# Sheet1.net
KiCad netlist of a schematic drawn in Altium Designer
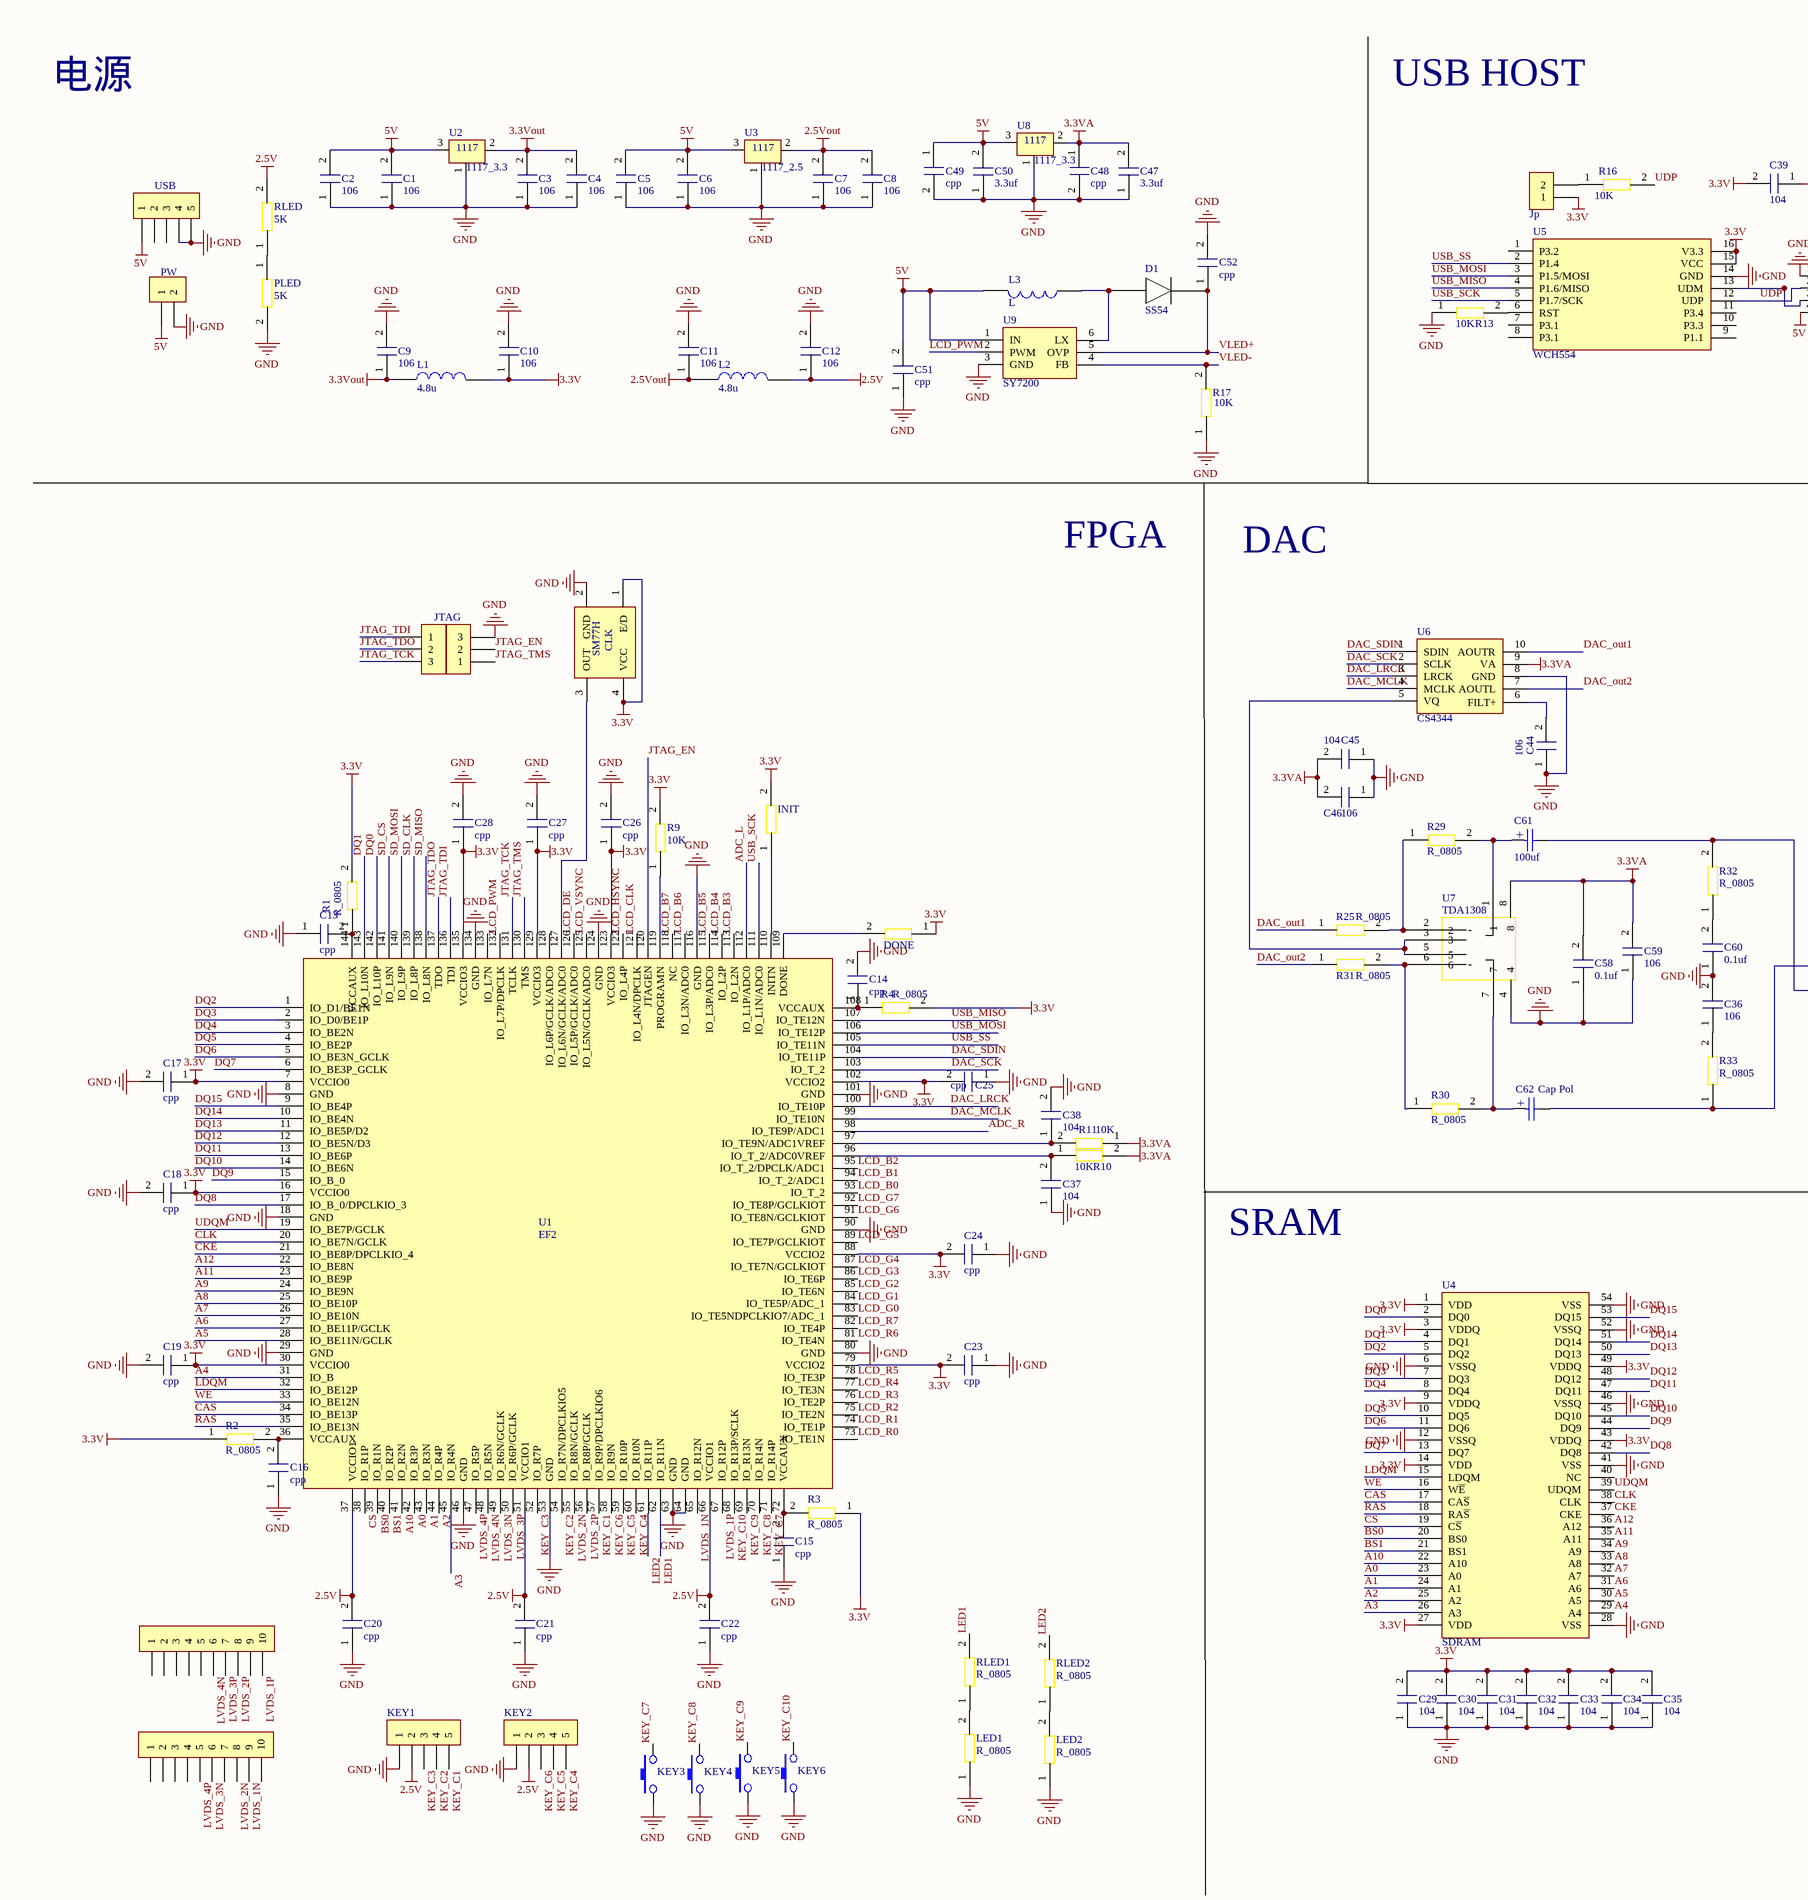
[diagram p0: Sheet1.SchDoc, left]
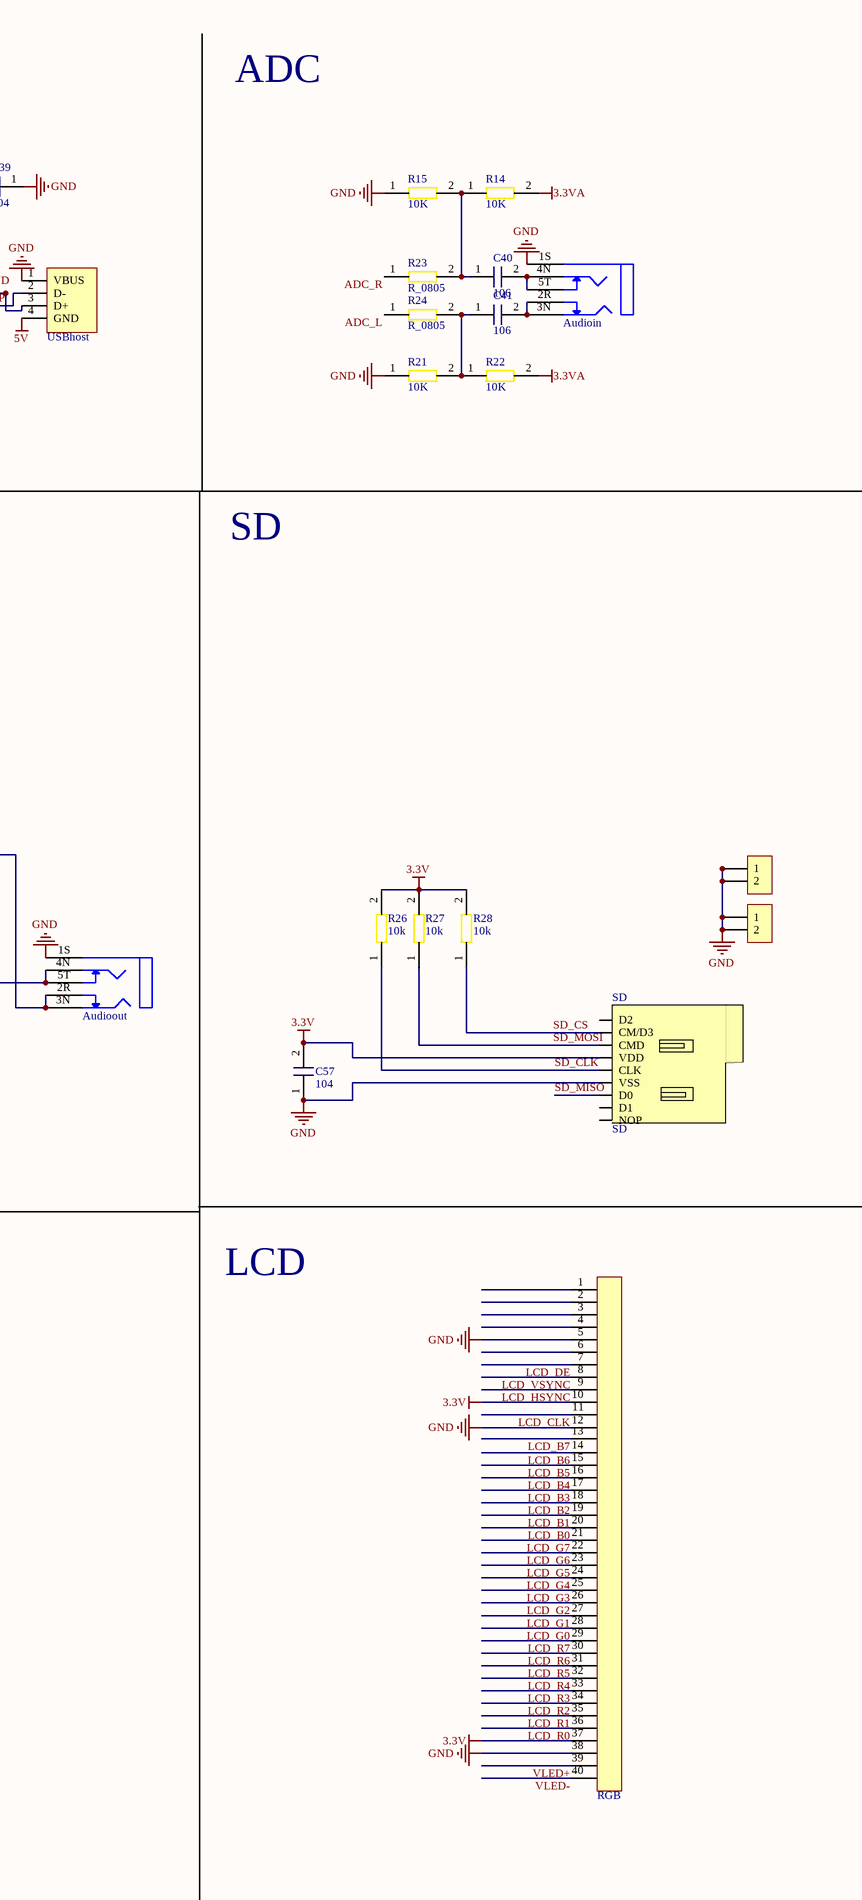
[diagram p1: Sheet1.SchDoc, right]

(export (version "E")
  (design (tool "Eeschema 10.0.6"))
  (components
    (comp (ref "Audioin") (value "Audio") (footprint "AUDIO") (libsource (lib "数字调频收音机") (part "Audio")))
    (comp (ref "Audioout") (value "Audio") (footprint "AUDIO") (libsource (lib "数字调频收音机") (part "Audio")))
    (comp (ref "brg") (value "CON10") (footprint "sip10") (libsource (lib "常用元件库") (part "CON10")))
    (comp (ref "brg1") (value "CON10") (footprint "sip10") (libsource (lib "常用元件库") (part "CON10")))
    (comp (ref "brg2") (value "CON2") (footprint "SIP2") (libsource (lib "常用元件库") (part "CON2")))
    (comp (ref "brg4") (value "CON2") (footprint "SIP2") (libsource (lib "常用元件库") (part "CON2")))
    (comp (ref "C1") (value "106") (footprint "电容器") (libsource (lib "常用") (part "cpp")))
    (comp (ref "C2") (value "106") (footprint "电容器") (libsource (lib "常用") (part "cpp")))
    (comp (ref "C3") (value "106") (footprint "电容器") (libsource (lib "常用") (part "cpp")))
    (comp (ref "C4") (value "106") (footprint "电容器") (libsource (lib "常用") (part "cpp")))
    (comp (ref "C5") (value "106") (footprint "电容器") (libsource (lib "常用") (part "cpp")))
    (comp (ref "C6") (value "106") (footprint "电容器") (libsource (lib "常用") (part "cpp")))
    (comp (ref "C7") (value "106") (footprint "电容器") (libsource (lib "常用") (part "cpp")))
    (comp (ref "C8") (value "106") (footprint "电容器") (libsource (lib "常用") (part "cpp")))
    (comp (ref "C9") (value "106") (footprint "电容器") (libsource (lib "常用") (part "cpp")))
    (comp (ref "C10") (value "106") (footprint "电容器") (libsource (lib "常用") (part "cpp")))
    (comp (ref "C11") (value "106") (footprint "电容器") (libsource (lib "常用") (part "cpp")))
    (comp (ref "C12") (value "106") (footprint "电容器") (libsource (lib "常用") (part "cpp")))
    (comp (ref "C13") (value "cpp") (footprint "电容器") (libsource (lib "常用") (part "cpp")))
    (comp (ref "C14") (value "cpp") (footprint "电容器") (libsource (lib "常用") (part "cpp")))
    (comp (ref "C15") (value "cpp") (footprint "电容器") (libsource (lib "常用") (part "cpp")))
    (comp (ref "C16") (value "cpp") (footprint "电容器") (libsource (lib "常用") (part "cpp")))
    (comp (ref "C17") (value "cpp") (footprint "电容器") (libsource (lib "常用") (part "cpp")))
    (comp (ref "C18") (value "cpp") (footprint "电容器") (libsource (lib "常用") (part "cpp")))
    (comp (ref "C19") (value "cpp") (footprint "电容器") (libsource (lib "常用") (part "cpp")))
    (comp (ref "C20") (value "cpp") (footprint "电容器") (libsource (lib "常用") (part "cpp")))
    (comp (ref "C21") (value "cpp") (footprint "电容器") (libsource (lib "常用") (part "cpp")))
    (comp (ref "C22") (value "cpp") (footprint "电容器") (libsource (lib "常用") (part "cpp")))
    (comp (ref "C23") (value "cpp") (footprint "电容器") (libsource (lib "常用") (part "cpp")))
    (comp (ref "C24") (value "cpp") (footprint "电容器") (libsource (lib "常用") (part "cpp")))
    (comp (ref "C25") (value "cpp") (footprint "电容器") (libsource (lib "常用") (part "cpp")))
    (comp (ref "C26") (value "cpp") (footprint "电容器") (libsource (lib "常用") (part "cpp")))
    (comp (ref "C27") (value "cpp") (footprint "电容器") (libsource (lib "常用") (part "cpp")))
    (comp (ref "C28") (value "cpp") (footprint "电容器") (libsource (lib "常用") (part "cpp")))
    (comp (ref "C29") (value "104") (footprint "电容器") (libsource (lib "常用") (part "cpp")))
    (comp (ref "C30") (value "104") (footprint "电容器") (libsource (lib "常用") (part "cpp")))
    (comp (ref "C31") (value "104") (footprint "电容器") (libsource (lib "常用") (part "cpp")))
    (comp (ref "C32") (value "104") (footprint "电容器") (libsource (lib "常用") (part "cpp")))
    (comp (ref "C33") (value "104") (footprint "电容器") (libsource (lib "常用") (part "cpp")))
    (comp (ref "C34") (value "104") (footprint "电容器") (libsource (lib "常用") (part "cpp")))
    (comp (ref "C35") (value "104") (footprint "电容器") (libsource (lib "常用") (part "cpp")))
    (comp (ref "C36") (value "106") (footprint "电容器") (libsource (lib "常用") (part "cpp")))
    (comp (ref "C37") (value "104") (footprint "电容器") (libsource (lib "常用") (part "cpp")))
    (comp (ref "C38") (value "104") (footprint "电容器") (libsource (lib "常用") (part "cpp")))
    (comp (ref "C39") (value "104") (footprint "电容器") (libsource (lib "常用") (part "cpp")))
    (comp (ref "C40") (value "106") (footprint "电容器") (libsource (lib "常用") (part "cpp")))
    (comp (ref "C41") (value "106") (footprint "电容器") (libsource (lib "常用") (part "cpp")))
    (comp (ref "C44") (value "106") (footprint "电容器") (libsource (lib "常用") (part "cpp")))
    (comp (ref "C45") (value "104") (footprint "电容器") (libsource (lib "常用") (part "cpp")))
    (comp (ref "C46") (value "106") (footprint "电容器") (libsource (lib "常用") (part "cpp")))
    (comp (ref "C47") (value "3.3uf") (footprint "电容器") (libsource (lib "常用") (part "cpp")))
    (comp (ref "C48") (value "cpp") (footprint "电容器") (libsource (lib "常用") (part "cpp")))
    (comp (ref "C49") (value "cpp") (footprint "电容器") (libsource (lib "常用") (part "cpp")))
    (comp (ref "C50") (value "3.3uf") (footprint "电容器") (libsource (lib "常用") (part "cpp")))
    (comp (ref "C51") (value "cpp") (footprint "电容器") (libsource (lib "常用") (part "cpp")))
    (comp (ref "C52") (value "cpp") (footprint "电容器") (libsource (lib "常用") (part "cpp")))
    (comp (ref "C57") (value "104") (footprint "电容器") (libsource (lib "常用") (part "cpp")))
    (comp (ref "C58") (value "0.1uf") (footprint "电容器") (libsource (lib "常用") (part "cpp")))
    (comp (ref "C59") (value "106") (footprint "电容器") (libsource (lib "常用") (part "cpp")))
    (comp (ref "C60") (value "0.1uf") (footprint "电容器") (libsource (lib "常用") (part "cpp")))
    (comp (ref "C61") (value "100uf") (footprint "RB.1/.2") (libsource (lib "常用元件库") (part "Cap Pol")))
    (comp (ref "C62") (value "Cap Pol") (footprint "RB.1/.2") (libsource (lib "常用元件库") (part "Cap Pol")))
    (comp (ref "CLK") (value "SM77H") (footprint "SM77H") (libsource (lib "常用") (part "SM77H")))
    (comp (ref "D1") (value "SS54") (footprint "SS54 - duplicate") (libsource (lib "常用") (part "SS54")))
    (comp (ref "DONE") (value "~") (footprint "R_0805") (libsource (lib "常用") (part "R_0805")))
    (comp (ref "INIT") (value "~") (footprint "R_0805") (libsource (lib "常用") (part "R_0805")))
    (comp (ref "Jp") (value "CON2") (footprint "SIP2") (libsource (lib "") (part "CON2_2")))
    (comp (ref "JTAG") (value "CON3") (footprint "SIP3") (libsource (lib "") (part "CON3_1")))
    (comp (ref "JTAG2") (value "CON3") (footprint "SIP3") (libsource (lib "常用元件库") (part "CON3")))
    (comp (ref "KEY1") (value "CON5") (footprint "SIP5") (libsource (lib "常用元件库") (part "CON5")))
    (comp (ref "KEY2") (value "CON5") (footprint "SIP5") (libsource (lib "常用元件库") (part "CON5")))
    (comp (ref "KEY3") (value "KEY") (footprint "AN66") (libsource (lib "数字调频收音机") (part "KEY")))
    (comp (ref "KEY4") (value "KEY") (footprint "AN66") (libsource (lib "数字调频收音机") (part "KEY")))
    (comp (ref "KEY5") (value "KEY") (footprint "AN66") (libsource (lib "数字调频收音机") (part "KEY")))
    (comp (ref "KEY6") (value "KEY") (footprint "AN66") (libsource (lib "数字调频收音机") (part "KEY")))
    (comp (ref "L1") (value "4.8u") (footprint "L") (libsource (lib "常用") (part "L")))
    (comp (ref "L2") (value "4.8u") (footprint "L") (libsource (lib "常用") (part "L")))
    (comp (ref "L3") (value "L") (footprint "L") (libsource (lib "常用") (part "L")))
    (comp (ref "LED1") (value "R_0805") (footprint "R_0805") (libsource (lib "常用") (part "R_0805")))
    (comp (ref "LED2") (value "R_0805") (footprint "R_0805") (libsource (lib "常用") (part "R_0805")))
    (comp (ref "PLED") (value "5K") (footprint "R_0805") (libsource (lib "常用") (part "R_0805")))
    (comp (ref "PW") (value "CON2") (footprint "SIP2") (libsource (lib "") (part "CON2_1")))
    (comp (ref "R1") (value "R_0805") (footprint "R_0805") (libsource (lib "常用") (part "R_0805")))
    (comp (ref "R2") (value "R_0805") (footprint "R_0805") (libsource (lib "常用") (part "R_0805")))
    (comp (ref "R3") (value "R_0805") (footprint "R_0805") (libsource (lib "常用") (part "R_0805")))
    (comp (ref "R4") (value "R_0805") (footprint "R_0805") (libsource (lib "常用") (part "R_0805")))
    (comp (ref "R9") (value "10K") (footprint "R_0805") (libsource (lib "常用") (part "R_0805")))
    (comp (ref "R10") (value "10K") (footprint "R_0805") (libsource (lib "常用") (part "R_0805")))
    (comp (ref "R11") (value "10K") (footprint "R_0805") (libsource (lib "常用") (part "R_0805")))
    (comp (ref "R13") (value "10K") (footprint "R_0805") (libsource (lib "常用") (part "R_0805")))
    (comp (ref "R14") (value "10K") (footprint "R_0805") (libsource (lib "常用") (part "R_0805")))
    (comp (ref "R15") (value "10K") (footprint "R_0805") (libsource (lib "常用") (part "R_0805")))
    (comp (ref "R16") (value "10K") (footprint "R_0805") (libsource (lib "常用") (part "R_0805")))
    (comp (ref "R17") (value "10K") (footprint "R_0805") (libsource (lib "常用") (part "R_0805")))
    (comp (ref "R21") (value "10K") (footprint "R_0805") (libsource (lib "常用") (part "R_0805")))
    (comp (ref "R22") (value "10K") (footprint "R_0805") (libsource (lib "常用") (part "R_0805")))
    (comp (ref "R23") (value "R_0805") (footprint "R_0805") (libsource (lib "常用") (part "R_0805")))
    (comp (ref "R24") (value "R_0805") (footprint "R_0805") (libsource (lib "常用") (part "R_0805")))
    (comp (ref "R25") (value "R_0805") (footprint "R_0805") (libsource (lib "常用") (part "R_0805")))
    (comp (ref "R26") (value "10k") (footprint "R_0805") (libsource (lib "常用") (part "R_0805")))
    (comp (ref "R27") (value "10k") (footprint "R_0805") (libsource (lib "常用") (part "R_0805")))
    (comp (ref "R28") (value "10k") (footprint "R_0805") (libsource (lib "常用") (part "R_0805")))
    (comp (ref "R29") (value "R_0805") (footprint "R_0805") (libsource (lib "常用") (part "R_0805")))
    (comp (ref "R30") (value "R_0805") (footprint "R_0805") (libsource (lib "常用") (part "R_0805")))
    (comp (ref "R31") (value "R_0805") (footprint "R_0805") (libsource (lib "常用") (part "R_0805")))
    (comp (ref "R32") (value "R_0805") (footprint "R_0805") (libsource (lib "常用") (part "R_0805")))
    (comp (ref "R33") (value "R_0805") (footprint "R_0805") (libsource (lib "常用") (part "R_0805")))
    (comp (ref "RGB") (value "PFC_40PIN") (footprint "FPC_40PIN") (libsource (lib "常用") (part "PFC_40PIN")))
    (comp (ref "RLED") (value "5K") (footprint "R_0805") (libsource (lib "常用") (part "R_0805")))
    (comp (ref "RLED1") (value "R_0805") (footprint "R_0805") (libsource (lib "常用") (part "R_0805")))
    (comp (ref "RLED2") (value "R_0805") (footprint "R_0805") (libsource (lib "常用") (part "R_0805")))
    (comp (ref "SD") (value "SD") (footprint "TF卡座") (libsource (lib "大二组原理图库") (part "TF卡座")))
    (comp (ref "U1") (value "EF2") (footprint "LQFP_EF2") (libsource (lib "常用") (part "EF2")))
    (comp (ref "U2") (value "1117_3.3") (footprint "SOT230P700X180-4N") (libsource (lib "常用") (part "1117")))
    (comp (ref "U3") (value "1117_2.5") (footprint "SOT230P700X180-4N") (libsource (lib "常用") (part "1117")))
    (comp (ref "U4") (value "SDRAM") (footprint "SDRAM") (libsource (lib "常用") (part "SDRAM")))
    (comp (ref "U5") (value "WCH554") (footprint "WCH554G") (libsource (lib "常用") (part "WCH554")))
    (comp (ref "U6") (value "CS4344") (footprint "SSOP10 _CS4344") (libsource (lib "常用") (part "CS4344")))
    (comp (ref "U7") (value "TDA1308") (footprint "TDA1308") (libsource (lib "常用") (part "TDA1308")))
    (comp (ref "U8") (value "1117_3.3") (footprint "SOT230P700X180-4N") (libsource (lib "常用") (part "1117")))
    (comp (ref "U9") (value "SY7200") (footprint "SOT23-6N") (libsource (lib "常用") (part "SY7200")))
    (comp (ref "USB") (value "USB") (footprint "micro-USB") (libsource (lib "大二组原理图库") (part "USB")))
    (comp (ref "USBhost") (value "USBhost") (footprint "USB-H") (libsource (lib "常用") (part "USBhost")))
  )
  (nets
    (net (code "1") (name "/A0") (class "Default")
      (node (ref "U1") (pin "42") (pinfunction "IO_R3P_42") (pintype "passive"))
      (node (ref "U4") (pin "23") (pinfunction "A0_23") (pintype "passive"))
    )
    (net (code "2") (name "/A1") (class "Default")
      (node (ref "U1") (pin "43") (pinfunction "IO_R3N_43") (pintype "passive"))
      (node (ref "U4") (pin "24") (pinfunction "A1_24") (pintype "passive"))
    )
    (net (code "3") (name "/A2") (class "Default")
      (node (ref "U1") (pin "44") (pinfunction "IO_R4P_44") (pintype "passive"))
      (node (ref "U4") (pin "25") (pinfunction "A2_25") (pintype "passive"))
    )
    (net (code "4") (name "/A3") (class "Default")
      (node (ref "U1") (pin "45") (pinfunction "IO_R4N_45") (pintype "passive"))
      (node (ref "U4") (pin "26") (pinfunction "A3_26") (pintype "passive"))
    )
    (net (code "5") (name "/A4") (class "Default")
      (node (ref "U1") (pin "31") (pinfunction "IO_B_31") (pintype "passive"))
      (node (ref "U4") (pin "29") (pinfunction "A4_29") (pintype "passive"))
    )
    (net (code "6") (name "/A5") (class "Default")
      (node (ref "U1") (pin "28") (pinfunction "IO_BE11N/GCLK_28") (pintype "passive"))
      (node (ref "U4") (pin "30") (pinfunction "A5_30") (pintype "passive"))
    )
    (net (code "7") (name "/A6") (class "Default")
      (node (ref "U1") (pin "27") (pinfunction "IO_BE11P/GCLK_27") (pintype "passive"))
      (node (ref "U4") (pin "31") (pinfunction "A6_31") (pintype "passive"))
    )
    (net (code "8") (name "/A7") (class "Default")
      (node (ref "U1") (pin "26") (pinfunction "IO_BE10N_26") (pintype "passive"))
      (node (ref "U4") (pin "32") (pinfunction "A7_32") (pintype "passive"))
    )
    (net (code "9") (name "/A8") (class "Default")
      (node (ref "U1") (pin "25") (pinfunction "IO_BE10P_25") (pintype "passive"))
      (node (ref "U4") (pin "33") (pinfunction "A8_33") (pintype "passive"))
    )
    (net (code "10") (name "/A9") (class "Default")
      (node (ref "U1") (pin "24") (pinfunction "IO_BE9N_24") (pintype "passive"))
      (node (ref "U4") (pin "34") (pinfunction "A9_34") (pintype "passive"))
    )
    (net (code "11") (name "/A10") (class "Default")
      (node (ref "U1") (pin "41") (pinfunction "IO_R2N_41") (pintype "passive"))
      (node (ref "U4") (pin "22") (pinfunction "A10_22") (pintype "passive"))
    )
    (net (code "12") (name "/A11") (class "Default")
      (node (ref "U1") (pin "23") (pinfunction "IO_BE9P_23") (pintype "passive"))
      (node (ref "U4") (pin "35") (pinfunction "A11_35") (pintype "passive"))
    )
    (net (code "13") (name "/A12") (class "Default")
      (node (ref "U1") (pin "22") (pinfunction "IO_BE8N_22") (pintype "passive"))
      (node (ref "U4") (pin "36") (pinfunction "A12_36") (pintype "passive"))
    )
    (net (code "14") (name "/ADC_L") (class "Default")
      (node (ref "R24") (pin "1") (pinfunction "1_1") (pintype "passive"))
      (node (ref "U1") (pin "112") (pinfunction "IO_L1P/ADC0_112") (pintype "passive"))
    )
    (net (code "15") (name "/ADC_R") (class "Default")
      (node (ref "R23") (pin "1") (pinfunction "1_1") (pintype "passive"))
      (node (ref "U1") (pin "98") (pinfunction "IO_TE9P/ADC1_98") (pintype "passive"))
    )
    (net (code "16") (name "/BS0") (class "Default")
      (node (ref "U1") (pin "39") (pinfunction "IO_R1N_39") (pintype "passive"))
      (node (ref "U4") (pin "20") (pinfunction "BS0_20") (pintype "passive"))
    )
    (net (code "17") (name "/BS1") (class "Default")
      (node (ref "U1") (pin "40") (pinfunction "IO_R2P_40") (pintype "passive"))
      (node (ref "U4") (pin "21") (pinfunction "BS1_21") (pintype "passive"))
    )
    (net (code "18") (name "/CAS") (class "Default")
      (node (ref "U1") (pin "34") (pinfunction "IO_BE13P_34") (pintype "passive"))
      (node (ref "U4") (pin "17") (pinfunction "CA~{S}_17") (pintype "passive"))
    )
    (net (code "19") (name "/CKE") (class "Default")
      (node (ref "U1") (pin "21") (pinfunction "IO_BE8P/DPCLKIO_4_21") (pintype "passive"))
      (node (ref "U4") (pin "37") (pinfunction "CKE_37") (pintype "passive"))
    )
    (net (code "20") (name "/CLK") (class "Default")
      (node (ref "U1") (pin "20") (pinfunction "IO_BE7N/GCLK_20") (pintype "passive"))
      (node (ref "U4") (pin "38") (pinfunction "CLK_38") (pintype "passive"))
    )
    (net (code "21") (name "/CS") (class "Default")
      (node (ref "U1") (pin "38") (pinfunction "IO_R1P_38") (pintype "passive"))
      (node (ref "U4") (pin "19") (pinfunction "C~{S}_19") (pintype "passive"))
    )
    (net (code "22") (name "/DAC_LRCK") (class "Default")
      (node (ref "U1") (pin "100") (pinfunction "IO_TE10P_100") (pintype "passive"))
      (node (ref "U6") (pin "3") (pinfunction "LRCK_3") (pintype "passive"))
    )
    (net (code "23") (name "/DAC_MCLK") (class "Default")
      (node (ref "U1") (pin "99") (pinfunction "IO_TE10N_99") (pintype "passive"))
      (node (ref "U6") (pin "4") (pinfunction "MCLK_4") (pintype "passive"))
    )
    (net (code "24") (name "/DAC_SCK") (class "Default")
      (node (ref "U1") (pin "103") (pinfunction "IO_T_2_103") (pintype "passive"))
      (node (ref "U6") (pin "2") (pinfunction "SCLK_2") (pintype "passive"))
    )
    (net (code "25") (name "/DAC_SDIN") (class "Default")
      (node (ref "U1") (pin "104") (pinfunction "IO_TE11P_104") (pintype "passive"))
      (node (ref "U6") (pin "1") (pinfunction "SDIN_1") (pintype "passive"))
    )
    (net (code "26") (name "/DAC_out1") (class "Default")
      (node (ref "R25") (pin "1") (pinfunction "1_1") (pintype "passive"))
      (node (ref "U6") (pin "10") (pinfunction "AOUTR_10") (pintype "passive"))
    )
    (net (code "27") (name "/DAC_out2") (class "Default")
      (node (ref "R31") (pin "1") (pinfunction "1_1") (pintype "passive"))
      (node (ref "U6") (pin "7") (pinfunction "AOUTL_7") (pintype "passive"))
    )
    (net (code "28") (name "/DQ0") (class "Default")
      (node (ref "U1") (pin "142") (pinfunction "IO_L10P_142") (pintype "passive"))
      (node (ref "U4") (pin "2") (pinfunction "DQ0_2") (pintype "passive"))
    )
    (net (code "29") (name "/DQ1") (class "Default")
      (node (ref "U1") (pin "143") (pinfunction "IO_L10N_143") (pintype "passive"))
      (node (ref "U4") (pin "4") (pinfunction "DQ1_4") (pintype "passive"))
    )
    (net (code "30") (name "/DQ2") (class "Default")
      (node (ref "U1") (pin "1") (pinfunction "IO_D1/BE1N_1") (pintype "passive"))
      (node (ref "U4") (pin "5") (pinfunction "DQ2_5") (pintype "passive"))
    )
    (net (code "31") (name "/DQ3") (class "Default")
      (node (ref "U1") (pin "2") (pinfunction "IO_D0/BE1P_2") (pintype "passive"))
      (node (ref "U4") (pin "7") (pinfunction "DQ3_7") (pintype "passive"))
    )
    (net (code "32") (name "/DQ4") (class "Default")
      (node (ref "U1") (pin "3") (pinfunction "IO_BE2N_3") (pintype "passive"))
      (node (ref "U4") (pin "8") (pinfunction "DQ4_8") (pintype "passive"))
    )
    (net (code "33") (name "/DQ5") (class "Default")
      (node (ref "U1") (pin "4") (pinfunction "IO_BE2P_4") (pintype "passive"))
      (node (ref "U4") (pin "10") (pinfunction "DQ5_10") (pintype "passive"))
    )
    (net (code "34") (name "/DQ6") (class "Default")
      (node (ref "U1") (pin "5") (pinfunction "IO_BE3N_GCLK_5") (pintype "passive"))
      (node (ref "U4") (pin "11") (pinfunction "DQ6_11") (pintype "passive"))
    )
    (net (code "35") (name "/DQ7") (class "Default")
      (node (ref "U1") (pin "6") (pinfunction "IO_BE3P_GCLK_6") (pintype "passive"))
      (node (ref "U4") (pin "13") (pinfunction "DQ7_13") (pintype "passive"))
    )
    (net (code "36") (name "/DQ8") (class "Default")
      (node (ref "U1") (pin "17") (pinfunction "IO_B_0/DPCLKIO_3_17") (pintype "passive"))
      (node (ref "U4") (pin "42") (pinfunction "DQ8_42") (pintype "passive"))
    )
    (net (code "37") (name "/DQ9") (class "Default")
      (node (ref "U1") (pin "15") (pinfunction "IO_B_0_15") (pintype "passive"))
      (node (ref "U4") (pin "44") (pinfunction "DQ9_44") (pintype "passive"))
    )
    (net (code "38") (name "/DQ10") (class "Default")
      (node (ref "U1") (pin "14") (pinfunction "IO_BE6N_14") (pintype "passive"))
      (node (ref "U4") (pin "45") (pinfunction "DQ10_45") (pintype "passive"))
    )
    (net (code "39") (name "/DQ11") (class "Default")
      (node (ref "U1") (pin "13") (pinfunction "IO_BE6P_13") (pintype "passive"))
      (node (ref "U4") (pin "47") (pinfunction "DQ11_47") (pintype "passive"))
    )
    (net (code "40") (name "/DQ12") (class "Default")
      (node (ref "U1") (pin "12") (pinfunction "IO_BE5N/D3_12") (pintype "passive"))
      (node (ref "U4") (pin "48") (pinfunction "DQ12_48") (pintype "passive"))
    )
    (net (code "41") (name "/DQ13") (class "Default")
      (node (ref "U1") (pin "11") (pinfunction "IO_BE5P/D2_11") (pintype "passive"))
      (node (ref "U4") (pin "50") (pinfunction "DQ13_50") (pintype "passive"))
    )
    (net (code "42") (name "/DQ14") (class "Default")
      (node (ref "U1") (pin "10") (pinfunction "IO_BE4N_10") (pintype "passive"))
      (node (ref "U4") (pin "51") (pinfunction "DQ14_51") (pintype "passive"))
    )
    (net (code "43") (name "/DQ15") (class "Default")
      (node (ref "U1") (pin "9") (pinfunction "IO_BE4P_9") (pintype "passive"))
      (node (ref "U4") (pin "53") (pinfunction "DQ15_53") (pintype "passive"))
    )
    (net (code "44") (name "/JTAG_EN") (class "Default")
      (node (ref "JTAG2") (pin "2") (pinfunction "2_2") (pintype "passive"))
      (node (ref "U1") (pin "120") (pinfunction "JTAGEN_120") (pintype "passive"))
    )
    (net (code "45") (name "/JTAG_TCK") (class "Default")
      (node (ref "JTAG") (pin "3") (pinfunction "3_3") (pintype "passive"))
      (node (ref "U1") (pin "131") (pinfunction "TCLK_131") (pintype "passive"))
    )
    (net (code "46") (name "/JTAG_TDI") (class "Default")
      (node (ref "JTAG") (pin "1") (pinfunction "1_1") (pintype "passive"))
      (node (ref "U1") (pin "136") (pinfunction "TDI_136") (pintype "passive"))
    )
    (net (code "47") (name "/JTAG_TDO") (class "Default")
      (node (ref "JTAG") (pin "2") (pinfunction "2_2") (pintype "passive"))
      (node (ref "U1") (pin "137") (pinfunction "TDO_137") (pintype "passive"))
    )
    (net (code "48") (name "/JTAG_TMS") (class "Default")
      (node (ref "JTAG2") (pin "1") (pinfunction "1_1") (pintype "passive"))
      (node (ref "U1") (pin "130") (pinfunction "TMS_130") (pintype "passive"))
    )
    (net (code "49") (name "/KEY_C1") (class "Default")
      (node (ref "KEY1") (pin "5") (pinfunction "5_5") (pintype "passive"))
      (node (ref "U1") (pin "57") (pinfunction "IO_R9P/DPCLKIO6_57") (pintype "passive"))
    )
    (net (code "50") (name "/KEY_C2") (class "Default")
      (node (ref "KEY1") (pin "4") (pinfunction "4_4") (pintype "passive"))
      (node (ref "U1") (pin "54") (pinfunction "IO_R7N/DPCLKIO5_54") (pintype "passive"))
    )
    (net (code "51") (name "/KEY_C3") (class "Default")
      (node (ref "KEY1") (pin "3") (pinfunction "3_3") (pintype "passive"))
      (node (ref "U1") (pin "52") (pinfunction "IO_R7P_52") (pintype "passive"))
    )
    (net (code "52") (name "/KEY_C4") (class "Default")
      (node (ref "KEY2") (pin "5") (pinfunction "5_5") (pintype "passive"))
      (node (ref "U1") (pin "60") (pinfunction "IO_R10N_60") (pintype "passive"))
    )
    (net (code "53") (name "/KEY_C5") (class "Default")
      (node (ref "KEY2") (pin "4") (pinfunction "4_4") (pintype "passive"))
      (node (ref "U1") (pin "59") (pinfunction "IO_R10P_59") (pintype "passive"))
    )
    (net (code "54") (name "/KEY_C6") (class "Default")
      (node (ref "KEY2") (pin "3") (pinfunction "3_3") (pintype "passive"))
      (node (ref "U1") (pin "58") (pinfunction "IO_R9N_58") (pintype "passive"))
    )
    (net (code "55") (name "/KEY_C7") (class "Default")
      (node (ref "KEY3") (pin "2") (pinfunction "2_2") (pintype "passive"))
      (node (ref "U1") (pin "71") (pinfunction "IO_R14P_71") (pintype "passive"))
    )
    (net (code "56") (name "/KEY_C8") (class "Default")
      (node (ref "KEY4") (pin "2") (pinfunction "2_2") (pintype "passive"))
      (node (ref "U1") (pin "70") (pinfunction "IO_R14N_70") (pintype "passive"))
    )
    (net (code "57") (name "/KEY_C9") (class "Default")
      (node (ref "KEY5") (pin "2") (pinfunction "2_2") (pintype "passive"))
      (node (ref "U1") (pin "69") (pinfunction "IO_R13N_69") (pintype "passive"))
    )
    (net (code "58") (name "/KEY_C10") (class "Default")
      (node (ref "KEY6") (pin "2") (pinfunction "2_2") (pintype "passive"))
      (node (ref "U1") (pin "68") (pinfunction "IO_R13P/SCLK_68") (pintype "passive"))
    )
    (net (code "59") (name "/LCD_B0") (class "Default")
      (node (ref "RGB") (pin "20") (pinfunction "20_20") (pintype "passive"))
      (node (ref "U1") (pin "93") (pinfunction "IO_T_2_93") (pintype "passive"))
    )
    (net (code "60") (name "/LCD_B1") (class "Default")
      (node (ref "RGB") (pin "19") (pinfunction "19_19") (pintype "passive"))
      (node (ref "U1") (pin "94") (pinfunction "IO_T_2/ADC1_94") (pintype "passive"))
    )
    (net (code "61") (name "/LCD_B2") (class "Default")
      (node (ref "RGB") (pin "18") (pinfunction "18_18") (pintype "passive"))
      (node (ref "U1") (pin "95") (pinfunction "IO_T_2/DPCLK/ADC1_95") (pintype "passive"))
    )
    (net (code "62") (name "/LCD_B3") (class "Default")
      (node (ref "RGB") (pin "17") (pinfunction "17_17") (pintype "passive"))
      (node (ref "U1") (pin "113") (pinfunction "IO_L2N_113") (pintype "passive"))
    )
    (net (code "63") (name "/LCD_B4") (class "Default")
      (node (ref "RGB") (pin "16") (pinfunction "16_16") (pintype "passive"))
      (node (ref "U1") (pin "114") (pinfunction "IO_L2P_114") (pintype "passive"))
    )
    (net (code "64") (name "/LCD_B5") (class "Default")
      (node (ref "RGB") (pin "15") (pinfunction "15_15") (pintype "passive"))
      (node (ref "U1") (pin "115") (pinfunction "IO_L3P/ADC0_115") (pintype "passive"))
    )
    (net (code "65") (name "/LCD_B6") (class "Default")
      (node (ref "RGB") (pin "14") (pinfunction "14_14") (pintype "passive"))
      (node (ref "U1") (pin "117") (pinfunction "IO_L3N/ADC0_117") (pintype "passive"))
    )
    (net (code "66") (name "/LCD_B7") (class "Default")
      (node (ref "RGB") (pin "13") (pinfunction "13_13") (pintype "passive"))
      (node (ref "U1") (pin "118") (pinfunction "NC_118") (pintype "passive"))
    )
    (net (code "67") (name "/LCD_CLK") (class "Default")
      (node (ref "RGB") (pin "11") (pinfunction "11_11") (pintype "passive"))
      (node (ref "U1") (pin "121") (pinfunction "IO_L4N/DPCLK_121") (pintype "passive"))
    )
    (net (code "68") (name "/LCD_DE") (class "Default")
      (node (ref "RGB") (pin "7") (pinfunction "7_7") (pintype "passive"))
      (node (ref "U1") (pin "126") (pinfunction "IO_L5P/GCLK/ADC0_126") (pintype "passive"))
    )
    (net (code "69") (name "/LCD_G0") (class "Default")
      (node (ref "RGB") (pin "28") (pinfunction "28_28") (pintype "passive"))
      (node (ref "U1") (pin "83") (pinfunction "IO_TE5NDPCLKIO7/ADC_1_83") (pintype "passive"))
    )
    (net (code "70") (name "/LCD_G1") (class "Default")
      (node (ref "RGB") (pin "27") (pinfunction "27_27") (pintype "passive"))
      (node (ref "U1") (pin "84") (pinfunction "IO_TE5P/ADC_1_84") (pintype "passive"))
    )
    (net (code "71") (name "/LCD_G2") (class "Default")
      (node (ref "RGB") (pin "26") (pinfunction "26_26") (pintype "passive"))
      (node (ref "U1") (pin "85") (pinfunction "IO_TE6N_85") (pintype "passive"))
    )
    (net (code "72") (name "/LCD_G3") (class "Default")
      (node (ref "RGB") (pin "25") (pinfunction "25_25") (pintype "passive"))
      (node (ref "U1") (pin "86") (pinfunction "IO_TE6P_86") (pintype "passive"))
    )
    (net (code "73") (name "/LCD_G4") (class "Default")
      (node (ref "RGB") (pin "24") (pinfunction "24_24") (pintype "passive"))
      (node (ref "U1") (pin "87") (pinfunction "IO_TE7N/GCLKIOT_87") (pintype "passive"))
    )
    (net (code "74") (name "/LCD_G5") (class "Default")
      (node (ref "RGB") (pin "23") (pinfunction "23_23") (pintype "passive"))
      (node (ref "U1") (pin "89") (pinfunction "IO_TE7P/GCLKIOT_89") (pintype "passive"))
    )
    (net (code "75") (name "/LCD_G6") (class "Default")
      (node (ref "RGB") (pin "22") (pinfunction "22_22") (pintype "passive"))
      (node (ref "U1") (pin "91") (pinfunction "IO_TE8N/GCLKIOT_91") (pintype "passive"))
    )
    (net (code "76") (name "/LCD_G7") (class "Default")
      (node (ref "RGB") (pin "21") (pinfunction "21_21") (pintype "passive"))
      (node (ref "U1") (pin "92") (pinfunction "IO_TE8P/GCLKIOT_92") (pintype "passive"))
    )
    (net (code "77") (name "/LCD_HSYNC") (class "Default")
      (node (ref "RGB") (pin "9") (pinfunction "9_9") (pintype "passive"))
      (node (ref "U1") (pin "122") (pinfunction "IO_L4P_122") (pintype "passive"))
    )
    (net (code "78") (name "/LCD_PWM") (class "Default")
      (node (ref "U1") (pin "132") (pinfunction "IO_L7P/DPCLK_132") (pintype "passive"))
      (node (ref "U9") (pin "2") (pinfunction "PWM_2") (pintype "passive"))
    )
    (net (code "79") (name "/LCD_R0") (class "Default")
      (node (ref "RGB") (pin "36") (pinfunction "36_36") (pintype "passive"))
      (node (ref "U1") (pin "73") (pinfunction "IO_TE1N_73") (pintype "passive"))
    )
    (net (code "80") (name "/LCD_R1") (class "Default")
      (node (ref "RGB") (pin "35") (pinfunction "35_35") (pintype "passive"))
      (node (ref "U1") (pin "74") (pinfunction "IO_TE1P_74") (pintype "passive"))
    )
    (net (code "81") (name "/LCD_R2") (class "Default")
      (node (ref "RGB") (pin "34") (pinfunction "34_34") (pintype "passive"))
      (node (ref "U1") (pin "75") (pinfunction "IO_TE2N_75") (pintype "passive"))
    )
    (net (code "82") (name "/LCD_R3") (class "Default")
      (node (ref "RGB") (pin "33") (pinfunction "33_33") (pintype "passive"))
      (node (ref "U1") (pin "76") (pinfunction "IO_TE2P_76") (pintype "passive"))
    )
    (net (code "83") (name "/LCD_R4") (class "Default")
      (node (ref "RGB") (pin "32") (pinfunction "32_32") (pintype "passive"))
      (node (ref "U1") (pin "77") (pinfunction "IO_TE3N_77") (pintype "passive"))
    )
    (net (code "84") (name "/LCD_R5") (class "Default")
      (node (ref "RGB") (pin "31") (pinfunction "31_31") (pintype "passive"))
      (node (ref "U1") (pin "78") (pinfunction "IO_TE3P_78") (pintype "passive"))
    )
    (net (code "85") (name "/LCD_R6") (class "Default")
      (node (ref "RGB") (pin "30") (pinfunction "30_30") (pintype "passive"))
      (node (ref "U1") (pin "81") (pinfunction "IO_TE4N_81") (pintype "passive"))
    )
    (net (code "86") (name "/LCD_R7") (class "Default")
      (node (ref "RGB") (pin "29") (pinfunction "29_29") (pintype "passive"))
      (node (ref "U1") (pin "82") (pinfunction "IO_TE4P_82") (pintype "passive"))
    )
    (net (code "87") (name "/LCD_VSYNC") (class "Default")
      (node (ref "RGB") (pin "8") (pinfunction "8_8") (pintype "passive"))
      (node (ref "U1") (pin "125") (pinfunction "IO_L5N/GCLK/ADC0_125") (pintype "passive"))
    )
    (net (code "88") (name "/LDQM") (class "Default")
      (node (ref "U1") (pin "32") (pinfunction "IO_BE12P_32") (pintype "passive"))
      (node (ref "U4") (pin "15") (pinfunction "LDQM_15") (pintype "passive"))
    )
    (net (code "89") (name "/LED1") (class "Default")
      (node (ref "RLED1") (pin "2") (pinfunction "2_2") (pintype "passive"))
      (node (ref "U1") (pin "62") (pinfunction "IO_R11N_62") (pintype "passive"))
    )
    (net (code "90") (name "/LED2") (class "Default")
      (node (ref "RLED2") (pin "2") (pinfunction "2_2") (pintype "passive"))
      (node (ref "U1") (pin "61") (pinfunction "IO_R11P_61") (pintype "passive"))
    )
    (net (code "91") (name "/LVDS_1N") (class "Default")
      (node (ref "U1") (pin "65") (pinfunction "IO_R12N_65") (pintype "passive"))
      (node (ref "brg1") (pin "9") (pinfunction "9_9") (pintype "passive"))
    )
    (net (code "92") (name "/LVDS_1P") (class "Default")
      (node (ref "U1") (pin "67") (pinfunction "IO_R12P_67") (pintype "passive"))
      (node (ref "brg") (pin "10") (pinfunction "10_10") (pintype "passive"))
    )
    (net (code "93") (name "/LVDS_2N") (class "Default")
      (node (ref "U1") (pin "55") (pinfunction "IO_R8N/GCLK_55") (pintype "passive"))
      (node (ref "brg1") (pin "8") (pinfunction "8_8") (pintype "passive"))
    )
    (net (code "94") (name "/LVDS_2P") (class "Default")
      (node (ref "U1") (pin "56") (pinfunction "IO_R8P/GCLK_56") (pintype "passive"))
      (node (ref "brg") (pin "8") (pinfunction "8_8") (pintype "passive"))
    )
    (net (code "95") (name "/LVDS_3N") (class "Default")
      (node (ref "U1") (pin "49") (pinfunction "IO_R6N/GCLK_49") (pintype "passive"))
      (node (ref "brg1") (pin "6") (pinfunction "6_6") (pintype "passive"))
    )
    (net (code "96") (name "/LVDS_3P") (class "Default")
      (node (ref "U1") (pin "50") (pinfunction "IO_R6P/GCLK_50") (pintype "passive"))
      (node (ref "brg") (pin "7") (pinfunction "7_7") (pintype "passive"))
    )
    (net (code "97") (name "/LVDS_4N") (class "Default")
      (node (ref "U1") (pin "48") (pinfunction "IO_R5N_48") (pintype "passive"))
      (node (ref "brg") (pin "6") (pinfunction "6_6") (pintype "passive"))
    )
    (net (code "98") (name "/LVDS_4P") (class "Default")
      (node (ref "U1") (pin "47") (pinfunction "IO_R5P_47") (pintype "passive"))
      (node (ref "brg1") (pin "5") (pinfunction "5_5") (pintype "passive"))
    )
    (net (code "99") (name "/RAS") (class "Default")
      (node (ref "U1") (pin "35") (pinfunction "IO_BE13N_35") (pintype "passive"))
      (node (ref "U4") (pin "18") (pinfunction "RA~{S}_18") (pintype "passive"))
    )
    (net (code "100") (name "/SD_CLK") (class "Default")
      (node (ref "R26") (pin "1") (pinfunction "1_1") (pintype "passive"))
      (node (ref "SD") (pin "5") (pinfunction "CLK_5") (pintype "passive"))
      (node (ref "U1") (pin "139") (pinfunction "IO_L8P_139") (pintype "passive"))
    )
    (net (code "101") (name "/SD_CS") (class "Default")
      (node (ref "R28") (pin "1") (pinfunction "1_1") (pintype "passive"))
      (node (ref "SD") (pin "2") (pinfunction "CM/D3_2") (pintype "passive"))
      (node (ref "U1") (pin "141") (pinfunction "IO_L9N_141") (pintype "passive"))
    )
    (net (code "102") (name "/SD_MISO") (class "Default")
      (node (ref "SD") (pin "7") (pinfunction "D0_7") (pintype "passive"))
      (node (ref "U1") (pin "138") (pinfunction "IO_L8N_138") (pintype "passive"))
    )
    (net (code "103") (name "/SD_MOSI") (class "Default")
      (node (ref "R27") (pin "1") (pinfunction "1_1") (pintype "passive"))
      (node (ref "SD") (pin "3") (pinfunction "CMD_3") (pintype "passive"))
      (node (ref "U1") (pin "140") (pinfunction "IO_L9P_140") (pintype "passive"))
    )
    (net (code "104") (name "/UDP") (class "Default")
      (node (ref "R16") (pin "2") (pinfunction "2_2") (pintype "passive"))
      (node (ref "U5") (pin "12") (pinfunction "UDP_12") (pintype "passive"))
      (node (ref "USBhost") (pin "2") (pinfunction "D-_2") (pintype "passive"))
    )
    (net (code "105") (name "/UDQM") (class "Default")
      (node (ref "U1") (pin "19") (pinfunction "IO_BE7P/GCLK_19") (pintype "passive"))
      (node (ref "U4") (pin "39") (pinfunction "UDQM_39") (pintype "passive"))
    )
    (net (code "106") (name "/USB_MISO") (class "Default")
      (node (ref "U1") (pin "107") (pinfunction "IO_TE12N_107") (pintype "passive"))
      (node (ref "U5") (pin "4") (pinfunction "P1.6/MISO_4") (pintype "passive"))
    )
    (net (code "107") (name "/USB_MOSI") (class "Default")
      (node (ref "U1") (pin "106") (pinfunction "IO_TE12P_106") (pintype "passive"))
      (node (ref "U5") (pin "3") (pinfunction "P1.5/MOSI_3") (pintype "passive"))
    )
    (net (code "108") (name "/USB_SCK") (class "Default")
      (node (ref "U1") (pin "111") (pinfunction "IO_L1N/ADC0_111") (pintype "passive"))
      (node (ref "U5") (pin "5") (pinfunction "P1.7/SCK_5") (pintype "passive"))
    )
    (net (code "109") (name "/USB_SS") (class "Default")
      (node (ref "U1") (pin "105") (pinfunction "IO_TE11N_105") (pintype "passive"))
      (node (ref "U5") (pin "2") (pinfunction "P1.4_2") (pintype "passive"))
    )
    (net (code "110") (name "/VLED+") (class "Default")
      (node (ref "C52") (pin "1") (pinfunction "c_1") (pintype "passive"))
      (node (ref "D1") (pin "1") (pinfunction "1_1") (pintype "passive"))
      (node (ref "RGB") (pin "39") (pinfunction "39_39") (pintype "passive"))
      (node (ref "U9") (pin "5") (pinfunction "OVP_5") (pintype "passive"))
    )
    (net (code "111") (name "/VLED-") (class "Default")
      (node (ref "R17") (pin "2") (pinfunction "2_2") (pintype "passive"))
      (node (ref "RGB") (pin "40") (pinfunction "40_40") (pintype "passive"))
      (node (ref "U9") (pin "4") (pinfunction "FB_4") (pintype "passive"))
    )
    (net (code "112") (name "/WE") (class "Default")
      (node (ref "U1") (pin "33") (pinfunction "IO_BE12N_33") (pintype "passive"))
      (node (ref "U4") (pin "16") (pinfunction "W~{E}_16") (pintype "passive"))
    )
    (net (code "113") (name "2.5V") (class "Default")
      (node (ref "C12") (pin "1") (pinfunction "c_1") (pintype "passive"))
      (node (ref "C20") (pin "2") (pinfunction "c+_2") (pintype "passive"))
      (node (ref "C21") (pin "2") (pinfunction "c+_2") (pintype "passive"))
      (node (ref "C22") (pin "2") (pinfunction "c+_2") (pintype "passive"))
      (node (ref "KEY1") (pin "2") (pinfunction "2_2") (pintype "passive"))
      (node (ref "KEY2") (pin "2") (pinfunction "2_2") (pintype "passive"))
      (node (ref "L2") (pin "1") (pinfunction "1_1") (pintype "passive"))
      (node (ref "RLED") (pin "2") (pinfunction "2_2") (pintype "passive"))
      (node (ref "U1") (pin "37") (pinfunction "VCCIO1_37") (pintype "passive"))
      (node (ref "U1") (pin "51") (pinfunction "VCCIO1_51") (pintype "passive"))
      (node (ref "U1") (pin "66") (pinfunction "VCCIO1_66") (pintype "passive"))
    )
    (net (code "114") (name "2.5Vout") (class "Default")
      (node (ref "C11") (pin "1") (pinfunction "c_1") (pintype "passive"))
      (node (ref "C7") (pin "2") (pinfunction "c+_2") (pintype "passive"))
      (node (ref "C8") (pin "2") (pinfunction "c+_2") (pintype "passive"))
      (node (ref "L2") (pin "2") (pinfunction "2_2") (pintype "passive"))
      (node (ref "U3") (pin "2") (pinfunction "OUT_2") (pintype "passive"))
    )
    (net (code "115") (name "3.3V") (class "Default")
      (node (ref "C10") (pin "1") (pinfunction "c_1") (pintype "passive"))
      (node (ref "C17") (pin "1") (pinfunction "c_1") (pintype "passive"))
      (node (ref "C18") (pin "1") (pinfunction "c_1") (pintype "passive"))
      (node (ref "C19") (pin "1") (pinfunction "c_1") (pintype "passive"))
      (node (ref "C23") (pin "2") (pinfunction "c+_2") (pintype "passive"))
      (node (ref "C24") (pin "2") (pinfunction "c+_2") (pintype "passive"))
      (node (ref "C25") (pin "2") (pinfunction "c+_2") (pintype "passive"))
      (node (ref "C26") (pin "1") (pinfunction "c_1") (pintype "passive"))
      (node (ref "C27") (pin "1") (pinfunction "c_1") (pintype "passive"))
      (node (ref "C28") (pin "1") (pinfunction "c_1") (pintype "passive"))
      (node (ref "C29") (pin "2") (pinfunction "c+_2") (pintype "passive"))
      (node (ref "C30") (pin "2") (pinfunction "c+_2") (pintype "passive"))
      (node (ref "C31") (pin "2") (pinfunction "c+_2") (pintype "passive"))
      (node (ref "C32") (pin "2") (pinfunction "c+_2") (pintype "passive"))
      (node (ref "C33") (pin "2") (pinfunction "c+_2") (pintype "passive"))
      (node (ref "C34") (pin "2") (pinfunction "c+_2") (pintype "passive"))
      (node (ref "C35") (pin "2") (pinfunction "c+_2") (pintype "passive"))
      (node (ref "C39") (pin "2") (pinfunction "c+_2") (pintype "passive"))
      (node (ref "C57") (pin "2") (pinfunction "c+_2") (pintype "passive"))
      (node (ref "CLK") (pin "1") (pinfunction "E/D_1") (pintype "passive"))
      (node (ref "CLK") (pin "4") (pinfunction "VCC_4") (pintype "passive"))
      (node (ref "DONE") (pin "1") (pinfunction "1_1") (pintype "passive"))
      (node (ref "INIT") (pin "2") (pinfunction "2_2") (pintype "passive"))
      (node (ref "Jp") (pin "1") (pinfunction "1_1") (pintype "passive"))
      (node (ref "L1") (pin "1") (pinfunction "1_1") (pintype "passive"))
      (node (ref "R1") (pin "2") (pinfunction "2_2") (pintype "passive"))
      (node (ref "R2") (pin "1") (pinfunction "1_1") (pintype "passive"))
      (node (ref "R26") (pin "2") (pinfunction "2_2") (pintype "passive"))
      (node (ref "R27") (pin "2") (pinfunction "2_2") (pintype "passive"))
      (node (ref "R28") (pin "2") (pinfunction "2_2") (pintype "passive"))
      (node (ref "R3") (pin "1") (pinfunction "1_1") (pintype "passive"))
      (node (ref "R4") (pin "2") (pinfunction "2_2") (pintype "passive"))
      (node (ref "R9") (pin "2") (pinfunction "2_2") (pintype "passive"))
      (node (ref "RGB") (pin "10") (pinfunction "10_10") (pintype "passive"))
      (node (ref "RGB") (pin "37") (pinfunction "37_37") (pintype "passive"))
      (node (ref "SD") (pin "4") (pinfunction "VDD_4") (pintype "passive"))
      (node (ref "U1") (pin "102") (pinfunction "VCCIO2_102") (pintype "passive"))
      (node (ref "U1") (pin "123") (pinfunction "VCCIO3_123") (pintype "passive"))
      (node (ref "U1") (pin "129") (pinfunction "VCCIO3_129") (pintype "passive"))
      (node (ref "U1") (pin "135") (pinfunction "VCCIO3_135") (pintype "passive"))
      (node (ref "U1") (pin "16") (pinfunction "VCCIO0_16") (pintype "passive"))
      (node (ref "U1") (pin "30") (pinfunction "VCCIO0_30") (pintype "passive"))
      (node (ref "U1") (pin "7") (pinfunction "VCCIO0_7") (pintype "passive"))
      (node (ref "U1") (pin "79") (pinfunction "VCCIO2_79") (pintype "passive"))
      (node (ref "U1") (pin "88") (pinfunction "VCCIO2_88") (pintype "passive"))
      (node (ref "U4") (pin "1") (pinfunction "VDD_1") (pintype "passive"))
      (node (ref "U4") (pin "14") (pinfunction "VDD_14") (pintype "passive"))
      (node (ref "U4") (pin "27") (pinfunction "VDD_27") (pintype "passive"))
      (node (ref "U4") (pin "3") (pinfunction "VDDQ_3") (pintype "passive"))
      (node (ref "U4") (pin "43") (pinfunction "VDDQ_43") (pintype "passive"))
      (node (ref "U4") (pin "49") (pinfunction "VDDQ_49") (pintype "passive"))
      (node (ref "U4") (pin "9") (pinfunction "VDDQ_9") (pintype "passive"))
      (node (ref "U5") (pin "15") (pinfunction "VCC_15") (pintype "passive"))
      (node (ref "U5") (pin "16") (pinfunction "V3.3_16") (pintype "passive"))
    )
    (net (code "116") (name "3.3VA") (class "Default")
      (node (ref "C45") (pin "2") (pinfunction "c+_2") (pintype "passive"))
      (node (ref "C46") (pin "2") (pinfunction "c+_2") (pintype "passive"))
      (node (ref "C47") (pin "2") (pinfunction "c+_2") (pintype "passive"))
      (node (ref "C48") (pin "1") (pinfunction "c_1") (pintype "passive"))
      (node (ref "C58") (pin "2") (pinfunction "c+_2") (pintype "passive"))
      (node (ref "C59") (pin "2") (pinfunction "c+_2") (pintype "passive"))
      (node (ref "R10") (pin "2") (pinfunction "2_2") (pintype "passive"))
      (node (ref "R11") (pin "1") (pinfunction "1_1") (pintype "passive"))
      (node (ref "R14") (pin "2") (pinfunction "2_2") (pintype "passive"))
      (node (ref "R22") (pin "2") (pinfunction "2_2") (pintype "passive"))
      (node (ref "U6") (pin "9") (pinfunction "VA_9") (pintype "passive"))
      (node (ref "U7") (pin "8") (pinfunction "8_8") (pintype "passive"))
      (node (ref "U8") (pin "2") (pinfunction "OUT_2") (pintype "passive"))
    )
    (net (code "117") (name "3.3Vout") (class "Default")
      (node (ref "C3") (pin "2") (pinfunction "c+_2") (pintype "passive"))
      (node (ref "C4") (pin "2") (pinfunction "c+_2") (pintype "passive"))
      (node (ref "C9") (pin "1") (pinfunction "c_1") (pintype "passive"))
      (node (ref "L1") (pin "2") (pinfunction "2_2") (pintype "passive"))
      (node (ref "U2") (pin "2") (pinfunction "OUT_2") (pintype "passive"))
    )
    (net (code "118") (name "5V") (class "Default")
      (node (ref "C1") (pin "2") (pinfunction "c+_2") (pintype "passive"))
      (node (ref "C2") (pin "2") (pinfunction "c+_2") (pintype "passive"))
      (node (ref "C49") (pin "1") (pinfunction "c_1") (pintype "passive"))
      (node (ref "C5") (pin "2") (pinfunction "c+_2") (pintype "passive"))
      (node (ref "C50") (pin "2") (pinfunction "c+_2") (pintype "passive"))
      (node (ref "C51") (pin "2") (pinfunction "c+_2") (pintype "passive"))
      (node (ref "C6") (pin "2") (pinfunction "c+_2") (pintype "passive"))
      (node (ref "L3") (pin "1") (pinfunction "1_1") (pintype "passive"))
      (node (ref "PW") (pin "1") (pinfunction "1_1") (pintype "passive"))
      (node (ref "U2") (pin "3") (pinfunction "IN_3") (pintype "passive"))
      (node (ref "U3") (pin "3") (pinfunction "IN_3") (pintype "passive"))
      (node (ref "U8") (pin "3") (pinfunction "IN_3") (pintype "passive"))
      (node (ref "U9") (pin "1") (pinfunction "IN_1") (pintype "passive"))
      (node (ref "USB") (pin "1") (pinfunction "1_1") (pintype "passive"))
      (node (ref "USBhost") (pin "4") (pinfunction "GND_4") (pintype "passive"))
    )
    (net (code "119") (name "GND") (class "Default")
      (node (ref "Audioin") (pin "1S") (pintype "passive"))
      (node (ref "Audioout") (pin "1S") (pintype "passive"))
      (node (ref "C1") (pin "1") (pinfunction "c_1") (pintype "passive"))
      (node (ref "C10") (pin "2") (pinfunction "c+_2") (pintype "passive"))
      (node (ref "C11") (pin "2") (pinfunction "c+_2") (pintype "passive"))
      (node (ref "C12") (pin "2") (pinfunction "c+_2") (pintype "passive"))
      (node (ref "C13") (pin "1") (pinfunction "c_1") (pintype "passive"))
      (node (ref "C14") (pin "2") (pinfunction "c+_2") (pintype "passive"))
      (node (ref "C15") (pin "1") (pinfunction "c_1") (pintype "passive"))
      (node (ref "C16") (pin "1") (pinfunction "c_1") (pintype "passive"))
      (node (ref "C17") (pin "2") (pinfunction "c+_2") (pintype "passive"))
      (node (ref "C18") (pin "2") (pinfunction "c+_2") (pintype "passive"))
      (node (ref "C19") (pin "2") (pinfunction "c+_2") (pintype "passive"))
      (node (ref "C2") (pin "1") (pinfunction "c_1") (pintype "passive"))
      (node (ref "C20") (pin "1") (pinfunction "c_1") (pintype "passive"))
      (node (ref "C21") (pin "1") (pinfunction "c_1") (pintype "passive"))
      (node (ref "C22") (pin "1") (pinfunction "c_1") (pintype "passive"))
      (node (ref "C23") (pin "1") (pinfunction "c_1") (pintype "passive"))
      (node (ref "C24") (pin "1") (pinfunction "c_1") (pintype "passive"))
      (node (ref "C25") (pin "1") (pinfunction "c_1") (pintype "passive"))
      (node (ref "C26") (pin "2") (pinfunction "c+_2") (pintype "passive"))
      (node (ref "C27") (pin "2") (pinfunction "c+_2") (pintype "passive"))
      (node (ref "C28") (pin "2") (pinfunction "c+_2") (pintype "passive"))
      (node (ref "C29") (pin "1") (pinfunction "c_1") (pintype "passive"))
      (node (ref "C3") (pin "1") (pinfunction "c_1") (pintype "passive"))
      (node (ref "C30") (pin "1") (pinfunction "c_1") (pintype "passive"))
      (node (ref "C31") (pin "1") (pinfunction "c_1") (pintype "passive"))
      (node (ref "C32") (pin "1") (pinfunction "c_1") (pintype "passive"))
      (node (ref "C33") (pin "1") (pinfunction "c_1") (pintype "passive"))
      (node (ref "C34") (pin "1") (pinfunction "c_1") (pintype "passive"))
      (node (ref "C35") (pin "1") (pinfunction "c_1") (pintype "passive"))
      (node (ref "C36") (pin "2") (pinfunction "c+_2") (pintype "passive"))
      (node (ref "C37") (pin "1") (pinfunction "c_1") (pintype "passive"))
      (node (ref "C38") (pin "2") (pinfunction "c+_2") (pintype "passive"))
      (node (ref "C39") (pin "1") (pinfunction "c_1") (pintype "passive"))
      (node (ref "C4") (pin "1") (pinfunction "c_1") (pintype "passive"))
      (node (ref "C44") (pin "1") (pinfunction "c_1") (pintype "passive"))
      (node (ref "C45") (pin "1") (pinfunction "c_1") (pintype "passive"))
      (node (ref "C46") (pin "1") (pinfunction "c_1") (pintype "passive"))
      (node (ref "C47") (pin "1") (pinfunction "c_1") (pintype "passive"))
      (node (ref "C48") (pin "2") (pinfunction "c+_2") (pintype "passive"))
      (node (ref "C49") (pin "2") (pinfunction "c+_2") (pintype "passive"))
      (node (ref "C5") (pin "1") (pinfunction "c_1") (pintype "passive"))
      (node (ref "C50") (pin "1") (pinfunction "c_1") (pintype "passive"))
      (node (ref "C51") (pin "1") (pinfunction "c_1") (pintype "passive"))
      (node (ref "C52") (pin "2") (pinfunction "c+_2") (pintype "passive"))
      (node (ref "C57") (pin "1") (pinfunction "c_1") (pintype "passive"))
      (node (ref "C58") (pin "1") (pinfunction "c_1") (pintype "passive"))
      (node (ref "C59") (pin "1") (pinfunction "c_1") (pintype "passive"))
      (node (ref "C6") (pin "1") (pinfunction "c_1") (pintype "passive"))
      (node (ref "C60") (pin "1") (pinfunction "c_1") (pintype "passive"))
      (node (ref "C7") (pin "1") (pinfunction "c_1") (pintype "passive"))
      (node (ref "C8") (pin "1") (pinfunction "c_1") (pintype "passive"))
      (node (ref "C9") (pin "2") (pinfunction "c+_2") (pintype "passive"))
      (node (ref "CLK") (pin "2") (pinfunction "GND_2") (pintype "passive"))
      (node (ref "JTAG2") (pin "3") (pinfunction "3_3") (pintype "passive"))
      (node (ref "KEY1") (pin "1") (pinfunction "1_1") (pintype "passive"))
      (node (ref "KEY2") (pin "1") (pinfunction "1_1") (pintype "passive"))
      (node (ref "KEY3") (pin "1") (pinfunction "1_1") (pintype "passive"))
      (node (ref "KEY4") (pin "1") (pinfunction "1_1") (pintype "passive"))
      (node (ref "KEY5") (pin "1") (pinfunction "1_1") (pintype "passive"))
      (node (ref "KEY6") (pin "1") (pinfunction "1_1") (pintype "passive"))
      (node (ref "LED1") (pin "1") (pinfunction "1_1") (pintype "passive"))
      (node (ref "LED2") (pin "1") (pinfunction "1_1") (pintype "passive"))
      (node (ref "PLED") (pin "2") (pinfunction "2_2") (pintype "passive"))
      (node (ref "PW") (pin "2") (pinfunction "2_2") (pintype "passive"))
      (node (ref "R13") (pin "1") (pinfunction "1_1") (pintype "passive"))
      (node (ref "R15") (pin "1") (pinfunction "1_1") (pintype "passive"))
      (node (ref "R17") (pin "1") (pinfunction "1_1") (pintype "passive"))
      (node (ref "R21") (pin "1") (pinfunction "1_1") (pintype "passive"))
      (node (ref "RGB") (pin "12") (pinfunction "12_12") (pintype "passive"))
      (node (ref "RGB") (pin "38") (pinfunction "38_38") (pintype "passive"))
      (node (ref "RGB") (pin "5") (pinfunction "5_5") (pintype "passive"))
      (node (ref "SD") (pin "6") (pinfunction "VSS_6") (pintype "passive"))
      (node (ref "U1") (pin "101") (pinfunction "GND_101") (pintype "passive"))
      (node (ref "U1") (pin "116") (pinfunction "GND_116") (pintype "passive"))
      (node (ref "U1") (pin "124") (pinfunction "GND_124") (pintype "passive"))
      (node (ref "U1") (pin "134") (pinfunction "GND_134") (pintype "passive"))
      (node (ref "U1") (pin "18") (pinfunction "GND_18") (pintype "passive"))
      (node (ref "U1") (pin "29") (pinfunction "GND_29") (pintype "passive"))
      (node (ref "U1") (pin "46") (pinfunction "GND_46") (pintype "passive"))
      (node (ref "U1") (pin "53") (pinfunction "GND_53") (pintype "passive"))
      (node (ref "U1") (pin "63") (pinfunction "GND_63") (pintype "passive"))
      (node (ref "U1") (pin "64") (pinfunction "GND_64") (pintype "passive"))
      (node (ref "U1") (pin "8") (pinfunction "GND_8") (pintype "passive"))
      (node (ref "U1") (pin "80") (pinfunction "GND_80") (pintype "passive"))
      (node (ref "U1") (pin "90") (pinfunction "GND_90") (pintype "passive"))
      (node (ref "U2") (pin "1") (pinfunction "ADJ_1") (pintype "passive"))
      (node (ref "U3") (pin "1") (pinfunction "ADJ_1") (pintype "passive"))
      (node (ref "U4") (pin "12") (pinfunction "VSSQ_12") (pintype "passive"))
      (node (ref "U4") (pin "28") (pinfunction "VSS_28") (pintype "passive"))
      (node (ref "U4") (pin "41") (pinfunction "VSS_41") (pintype "passive"))
      (node (ref "U4") (pin "46") (pinfunction "VSSQ_46") (pintype "passive"))
      (node (ref "U4") (pin "52") (pinfunction "VSSQ_52") (pintype "passive"))
      (node (ref "U4") (pin "54") (pinfunction "VSS_54") (pintype "passive"))
      (node (ref "U4") (pin "6") (pinfunction "VSSQ_6") (pintype "passive"))
      (node (ref "U5") (pin "14") (pinfunction "GND_14") (pintype "passive"))
      (node (ref "U6") (pin "8") (pinfunction "GND_8") (pintype "passive"))
      (node (ref "U7") (pin "4") (pinfunction "4_4") (pintype "passive"))
      (node (ref "U8") (pin "1") (pinfunction "ADJ_1") (pintype "passive"))
      (node (ref "U9") (pin "3") (pinfunction "GND_3") (pintype "passive"))
      (node (ref "USB") (pin "4") (pinfunction "4_4") (pintype "passive"))
      (node (ref "USB") (pin "5") (pinfunction "5_5") (pintype "passive"))
      (node (ref "USBhost") (pin "1") (pinfunction "VBUS_1") (pintype "passive"))
      (node (ref "brg2") (pin "1") (pinfunction "1_1") (pintype "passive"))
      (node (ref "brg2") (pin "2") (pinfunction "2_2") (pintype "passive"))
      (node (ref "brg4") (pin "1") (pinfunction "1_1") (pintype "passive"))
      (node (ref "brg4") (pin "2") (pinfunction "2_2") (pintype "passive"))
    )
    (net (code "120") (name "Net-(Audioout-Pad2R)") (class "Default")
      (node (ref "Audioout") (pin "2R") (pintype "passive"))
      (node (ref "Audioout") (pin "3N") (pintype "passive"))
      (node (ref "C61") (pin "2") (pinfunction "2_2") (pintype "passive"))
      (node (ref "R32") (pin "2") (pinfunction "2_2") (pintype "passive"))
    )
    (net (code "121") (name "Net-(Audioout-Pad4N)") (class "Default")
      (node (ref "Audioout") (pin "4N") (pintype "passive"))
      (node (ref "Audioout") (pin "5T") (pintype "passive"))
      (node (ref "C62") (pin "2") (pinfunction "2_2") (pintype "passive"))
      (node (ref "R33") (pin "1") (pinfunction "1_1") (pintype "passive"))
    )
    (net (code "122") (name "Net-(C13-c+)") (class "Default")
      (node (ref "C13") (pin "2") (pinfunction "c+_2") (pintype "passive"))
      (node (ref "R1") (pin "1") (pinfunction "1_1") (pintype "passive"))
      (node (ref "U1") (pin "144") (pinfunction "VCCAUX_144") (pintype "passive"))
    )
    (net (code "123") (name "Net-(C14-c)") (class "Default")
      (node (ref "C14") (pin "1") (pinfunction "c_1") (pintype "passive"))
      (node (ref "R4") (pin "1") (pinfunction "1_1") (pintype "passive"))
      (node (ref "U1") (pin "108") (pinfunction "VCCAUX_108") (pintype "passive"))
    )
    (net (code "124") (name "Net-(C15-c+)") (class "Default")
      (node (ref "C15") (pin "2") (pinfunction "c+_2") (pintype "passive"))
      (node (ref "R3") (pin "2") (pinfunction "2_2") (pintype "passive"))
      (node (ref "U1") (pin "72") (pinfunction "VCCAUX_72") (pintype "passive"))
    )
    (net (code "125") (name "Net-(C16-c+)") (class "Default")
      (node (ref "C16") (pin "2") (pinfunction "c+_2") (pintype "passive"))
      (node (ref "R2") (pin "2") (pinfunction "2_2") (pintype "passive"))
      (node (ref "U1") (pin "36") (pinfunction "VCCAUX_36") (pintype "passive"))
    )
    (net (code "126") (name "Net-(C36-c)") (class "Default")
      (node (ref "C36") (pin "1") (pinfunction "c_1") (pintype "passive"))
      (node (ref "R33") (pin "2") (pinfunction "2_2") (pintype "passive"))
    )
    (net (code "127") (name "Net-(C37-c+)") (class "Default")
      (node (ref "C37") (pin "2") (pinfunction "c+_2") (pintype "passive"))
      (node (ref "R10") (pin "1") (pinfunction "1_1") (pintype "passive"))
      (node (ref "U1") (pin "96") (pinfunction "IO_T_2/ADC0VREF_96") (pintype "passive"))
    )
    (net (code "128") (name "Net-(C38-c)") (class "Default")
      (node (ref "C38") (pin "1") (pinfunction "c_1") (pintype "passive"))
      (node (ref "R11") (pin "2") (pinfunction "2_2") (pintype "passive"))
      (node (ref "U1") (pin "97") (pinfunction "IO_TE9N/ADC1VREF_97") (pintype "passive"))
    )
    (net (code "129") (name "Net-(C40-c)") (class "Default")
      (node (ref "C40") (pin "1") (pinfunction "c_1") (pintype "passive"))
      (node (ref "R14") (pin "1") (pinfunction "1_1") (pintype "passive"))
      (node (ref "R15") (pin "2") (pinfunction "2_2") (pintype "passive"))
      (node (ref "R23") (pin "2") (pinfunction "2_2") (pintype "passive"))
    )
    (net (code "130") (name "Net-(C40-c+)") (class "Default")
      (node (ref "Audioin") (pin "4N") (pintype "passive"))
      (node (ref "Audioin") (pin "5T") (pintype "passive"))
      (node (ref "C40") (pin "2") (pinfunction "c+_2") (pintype "passive"))
    )
    (net (code "131") (name "Net-(C41-c)") (class "Default")
      (node (ref "C41") (pin "1") (pinfunction "c_1") (pintype "passive"))
      (node (ref "R21") (pin "2") (pinfunction "2_2") (pintype "passive"))
      (node (ref "R22") (pin "1") (pinfunction "1_1") (pintype "passive"))
      (node (ref "R24") (pin "2") (pinfunction "2_2") (pintype "passive"))
    )
    (net (code "132") (name "Net-(C41-c+)") (class "Default")
      (node (ref "Audioin") (pin "2R") (pintype "passive"))
      (node (ref "Audioin") (pin "3N") (pintype "passive"))
      (node (ref "C41") (pin "2") (pinfunction "c+_2") (pintype "passive"))
    )
    (net (code "133") (name "Net-(C44-c+)") (class "Default")
      (node (ref "C44") (pin "2") (pinfunction "c+_2") (pintype "passive"))
      (node (ref "U6") (pin "6") (pinfunction "FILT+_6") (pintype "passive"))
    )
    (net (code "134") (name "Net-(C60-c+)") (class "Default")
      (node (ref "C60") (pin "2") (pinfunction "c+_2") (pintype "passive"))
      (node (ref "R32") (pin "1") (pinfunction "1_1") (pintype "passive"))
    )
    (net (code "135") (name "Net-(C61-Pad1)") (class "Default")
      (node (ref "C61") (pin "1") (pinfunction "1_1") (pintype "passive"))
      (node (ref "R29") (pin "2") (pinfunction "2_2") (pintype "passive"))
      (node (ref "U7") (pin "1") (pinfunction "1_1") (pintype "passive"))
    )
    (net (code "136") (name "Net-(C62-Pad1)") (class "Default")
      (node (ref "C62") (pin "1") (pinfunction "1_1") (pintype "passive"))
      (node (ref "R30") (pin "2") (pinfunction "2_2") (pintype "passive"))
      (node (ref "U7") (pin "7") (pinfunction "7_7") (pintype "passive"))
    )
    (net (code "137") (name "Net-(CLK-OUT)") (class "Default")
      (node (ref "CLK") (pin "3") (pinfunction "OUT_3") (pintype "passive"))
      (node (ref "U1") (pin "127") (pinfunction "IO_L6N/GCLK/ADC0_127") (pintype "passive"))
    )
    (net (code "138") (name "Net-(Jp-Pad2)") (class "Default")
      (node (ref "Jp") (pin "2") (pinfunction "2_2") (pintype "passive"))
      (node (ref "R16") (pin "1") (pinfunction "1_1") (pintype "passive"))
    )
    (net (code "139") (name "Net-(LED1-Pad2)") (class "Default")
      (node (ref "LED1") (pin "2") (pinfunction "2_2") (pintype "passive"))
      (node (ref "RLED1") (pin "1") (pinfunction "1_1") (pintype "passive"))
    )
    (net (code "140") (name "Net-(LED2-Pad2)") (class "Default")
      (node (ref "LED2") (pin "2") (pinfunction "2_2") (pintype "passive"))
      (node (ref "RLED2") (pin "1") (pinfunction "1_1") (pintype "passive"))
    )
    (net (code "141") (name "Net-(PLED-Pad1)") (class "Default")
      (node (ref "PLED") (pin "1") (pinfunction "1_1") (pintype "passive"))
      (node (ref "RLED") (pin "1") (pinfunction "1_1") (pintype "passive"))
    )
    (net (code "142") (name "Net-(R25-Pad2)") (class "Default")
      (node (ref "R25") (pin "2") (pinfunction "2_2") (pintype "passive"))
      (node (ref "R29") (pin "1") (pinfunction "1_1") (pintype "passive"))
      (node (ref "U7") (pin "2") (pinfunction "2_2") (pintype "passive"))
    )
    (net (code "143") (name "Net-(R30-Pad1)") (class "Default")
      (node (ref "R30") (pin "1") (pinfunction "1_1") (pintype "passive"))
      (node (ref "R31") (pin "2") (pinfunction "2_2") (pintype "passive"))
      (node (ref "U7") (pin "6") (pinfunction "6_6") (pintype "passive"))
    )
    (net (code "144") (name "Net-(U1-DONE)") (class "Default")
      (node (ref "DONE") (pin "2") (pinfunction "2_2") (pintype "passive"))
      (node (ref "U1") (pin "109") (pinfunction "DONE_109") (pintype "passive"))
    )
    (net (code "145") (name "Net-(U1-INITN)") (class "Default")
      (node (ref "INIT") (pin "1") (pinfunction "1_1") (pintype "passive"))
      (node (ref "U1") (pin "110") (pinfunction "INITN_110") (pintype "passive"))
    )
    (net (code "146") (name "Net-(U1-PROGRAMN)") (class "Default")
      (node (ref "R9") (pin "1") (pinfunction "1_1") (pintype "passive"))
      (node (ref "U1") (pin "119") (pinfunction "PROGRAMN_119") (pintype "passive"))
    )
    (net (code "147") (name "Net-(U5-RST)") (class "Default")
      (node (ref "R13") (pin "2") (pinfunction "2_2") (pintype "passive"))
      (node (ref "U5") (pin "6") (pinfunction "RST_6") (pintype "passive"))
    )
    (net (code "148") (name "Net-(U5-UDM)") (class "Default")
      (node (ref "U5") (pin "13") (pinfunction "UDM_13") (pintype "passive"))
      (node (ref "USBhost") (pin "3") (pinfunction "D+_3") (pintype "passive"))
    )
    (net (code "149") (name "Net-(U6-VQ)") (class "Default")
      (node (ref "U6") (pin "5") (pinfunction "VQ_5") (pintype "passive"))
      (node (ref "U7") (pin "3") (pinfunction "3_3") (pintype "passive"))
      (node (ref "U7") (pin "5") (pinfunction "5_5") (pintype "passive"))
    )
    (net (code "150") (name "Net-(U9-LX)") (class "Default")
      (node (ref "D1") (pin "2") (pinfunction "2_2") (pintype "passive"))
      (node (ref "L3") (pin "2") (pinfunction "2_2") (pintype "passive"))
      (node (ref "U9") (pin "6") (pinfunction "LX_6") (pintype "passive"))
    )
    (net (code "151") (name "unconnected-(RGB-Pad1)") (class "Default")
      (node (ref "RGB") (pin "1") (pinfunction "1_1") (pintype "passive"))
    )
    (net (code "152") (name "unconnected-(RGB-Pad2)") (class "Default")
      (node (ref "RGB") (pin "2") (pinfunction "2_2") (pintype "passive"))
    )
    (net (code "153") (name "unconnected-(RGB-Pad3)") (class "Default")
      (node (ref "RGB") (pin "3") (pinfunction "3_3") (pintype "passive"))
    )
    (net (code "154") (name "unconnected-(RGB-Pad4)") (class "Default")
      (node (ref "RGB") (pin "4") (pinfunction "4_4") (pintype "passive"))
    )
    (net (code "155") (name "unconnected-(RGB-Pad6)") (class "Default")
      (node (ref "RGB") (pin "6") (pinfunction "6_6") (pintype "passive"))
    )
    (net (code "156") (name "unconnected-(SD-D1-Pad8)") (class "Default")
      (node (ref "SD") (pin "8") (pinfunction "D1_8") (pintype "passive"))
    )
    (net (code "157") (name "unconnected-(SD-D2-Pad1)") (class "Default")
      (node (ref "SD") (pin "1") (pinfunction "D2_1") (pintype "passive"))
    )
    (net (code "158") (name "unconnected-(SD-NOP-Pad9)") (class "Default")
      (node (ref "SD") (pin "9") (pinfunction "NOP_9") (pintype "passive"))
    )
    (net (code "159") (name "unconnected-(U1-IO_L6P{slash}GCLK{slash}ADC0-Pad128)") (class "Default")
      (node (ref "U1") (pin "128") (pinfunction "IO_L6P/GCLK/ADC0_128") (pintype "passive"))
    )
    (net (code "160") (name "unconnected-(U1-IO_L7N-Pad133)") (class "Default")
      (node (ref "U1") (pin "133") (pinfunction "IO_L7N_133") (pintype "passive"))
    )
    (net (code "161") (name "unconnected-(U4-NC-Pad40)") (class "Default")
      (node (ref "U4") (pin "40") (pinfunction "NC_40") (pintype "passive"))
    )
    (net (code "162") (name "unconnected-(U5-P1.1-Pad9)") (class "Default")
      (node (ref "U5") (pin "9") (pinfunction "P1.1_9") (pintype "passive"))
    )
    (net (code "163") (name "unconnected-(U5-P3.1-Pad7)") (class "Default")
      (node (ref "U5") (pin "7") (pinfunction "P3.1_7") (pintype "passive"))
    )
    (net (code "164") (name "unconnected-(U5-P3.1-Pad8)") (class "Default")
      (node (ref "U5") (pin "8") (pinfunction "P3.1_8") (pintype "passive"))
    )
    (net (code "165") (name "unconnected-(U5-P3.2-Pad1)") (class "Default")
      (node (ref "U5") (pin "1") (pinfunction "P3.2_1") (pintype "passive"))
    )
    (net (code "166") (name "unconnected-(U5-P3.3-Pad10)") (class "Default")
      (node (ref "U5") (pin "10") (pinfunction "P3.3_10") (pintype "passive"))
    )
    (net (code "167") (name "unconnected-(U5-P3.4-Pad11)") (class "Default")
      (node (ref "U5") (pin "11") (pinfunction "P3.4_11") (pintype "passive"))
    )
    (net (code "168") (name "unconnected-(USB-Pad2)") (class "Default")
      (node (ref "USB") (pin "2") (pinfunction "2_2") (pintype "passive"))
    )
    (net (code "169") (name "unconnected-(USB-Pad3)") (class "Default")
      (node (ref "USB") (pin "3") (pinfunction "3_3") (pintype "passive"))
    )
    (net (code "170") (name "unconnected-(brg-Pad1)") (class "Default")
      (node (ref "brg") (pin "1") (pinfunction "1_1") (pintype "passive"))
    )
    (net (code "171") (name "unconnected-(brg-Pad2)") (class "Default")
      (node (ref "brg") (pin "2") (pinfunction "2_2") (pintype "passive"))
    )
    (net (code "172") (name "unconnected-(brg-Pad3)") (class "Default")
      (node (ref "brg") (pin "3") (pinfunction "3_3") (pintype "passive"))
    )
    (net (code "173") (name "unconnected-(brg-Pad4)") (class "Default")
      (node (ref "brg") (pin "4") (pinfunction "4_4") (pintype "passive"))
    )
    (net (code "174") (name "unconnected-(brg-Pad5)") (class "Default")
      (node (ref "brg") (pin "5") (pinfunction "5_5") (pintype "passive"))
    )
    (net (code "175") (name "unconnected-(brg-Pad9)") (class "Default")
      (node (ref "brg") (pin "9") (pinfunction "9_9") (pintype "passive"))
    )
    (net (code "176") (name "unconnected-(brg1-Pad1)") (class "Default")
      (node (ref "brg1") (pin "1") (pinfunction "1_1") (pintype "passive"))
    )
    (net (code "177") (name "unconnected-(brg1-Pad2)") (class "Default")
      (node (ref "brg1") (pin "2") (pinfunction "2_2") (pintype "passive"))
    )
    (net (code "178") (name "unconnected-(brg1-Pad3)") (class "Default")
      (node (ref "brg1") (pin "3") (pinfunction "3_3") (pintype "passive"))
    )
    (net (code "179") (name "unconnected-(brg1-Pad4)") (class "Default")
      (node (ref "brg1") (pin "4") (pinfunction "4_4") (pintype "passive"))
    )
    (net (code "180") (name "unconnected-(brg1-Pad7)") (class "Default")
      (node (ref "brg1") (pin "7") (pinfunction "7_7") (pintype "passive"))
    )
    (net (code "181") (name "unconnected-(brg1-Pad10)") (class "Default")
      (node (ref "brg1") (pin "10") (pinfunction "10_10") (pintype "passive"))
    )
  )
)
